# midi_io.net
KiCad netlist of a schematic drawn in EAGLE
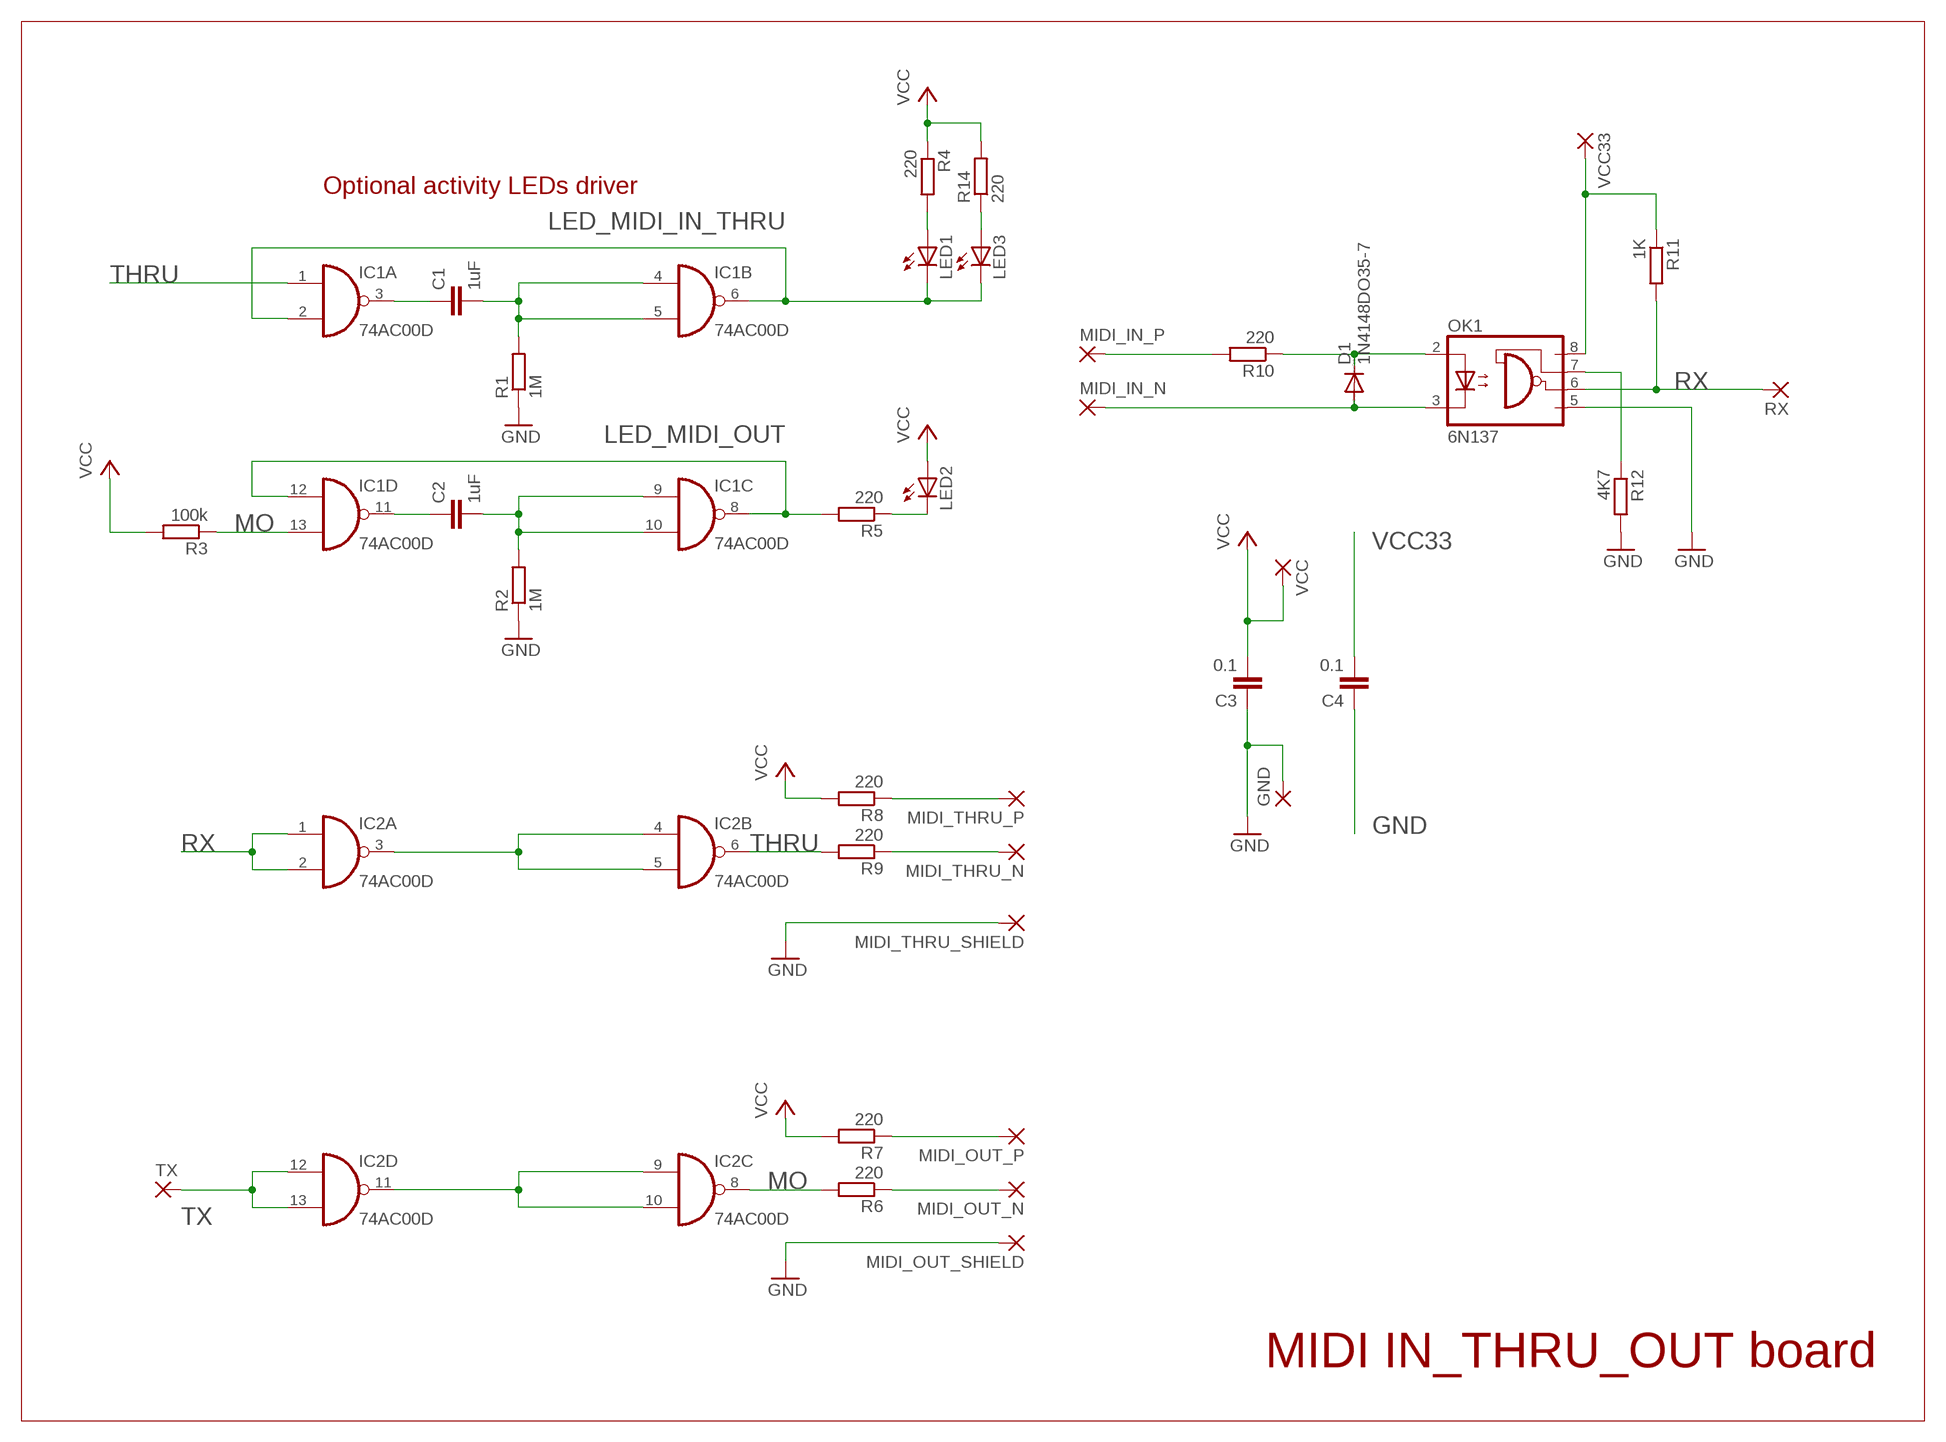
[diagram p0: schematic, sheet 1]

(export (version "E")
  (design (tool "Eeschema 10.0.6"))
  (components
    (comp (ref "C1")
      (value "1uF")
      (footprint "eagle-import:C0805")
      (libsource (lib "eagle-import") (part "C-EUC0805"))
    )
    (comp (ref "C2")
      (value "1uF")
      (footprint "eagle-import:C0805")
      (libsource (lib "eagle-import") (part "C-EUC0805"))
    )
    (comp (ref "C3")
      (value "0.1")
      (footprint "eagle-import:C0805")
      (libsource (lib "eagle-import") (part "C-EUC0805"))
    )
    (comp (ref "C4")
      (value "0.1")
      (footprint "eagle-import:C0805")
      (libsource (lib "eagle-import") (part "C-EUC0805"))
    )
    (comp (ref "D1")
      (value "1N4148DO35-7")
      (footprint "eagle-import:DO35-7")
      (libsource (lib "eagle-import") (part "1N4148DO35-7"))
    )
    (comp (ref "GND")
      (value "1,6/0,8")
      (footprint "eagle-import:1,6_0,8")
      (libsource (lib "eagle-import") (part "1,6/0,8"))
    )
    (comp (ref "IC1")
      (value "74AC00D")
      (footprint "eagle-import:SO14")
      (libsource (lib "eagle-import") (part "7400DAC"))
    )
    (comp (ref "IC2")
      (value "74AC00D")
      (footprint "eagle-import:SO14")
      (libsource (lib "eagle-import") (part "7400DAC"))
    )
    (comp (ref "LED1")
      (value "LED3MM")
      (footprint "eagle-import:LED3MM")
      (libsource (lib "eagle-import") (part "LED3MM"))
    )
    (comp (ref "LED2")
      (value "LED3MM")
      (footprint "eagle-import:LED3MM")
      (libsource (lib "eagle-import") (part "LED3MM"))
    )
    (comp (ref "LED3")
      (value "LED3MM")
      (footprint "eagle-import:LED3MM")
      (libsource (lib "eagle-import") (part "LED3MM"))
    )
    (comp (ref "MIDI_IN_N")
      (value "1,6/0,8")
      (footprint "eagle-import:1,6_0,8")
      (libsource (lib "eagle-import") (part "1,6/0,8"))
    )
    (comp (ref "MIDI_IN_P")
      (value "1,6/0,8")
      (footprint "eagle-import:1,6_0,8")
      (libsource (lib "eagle-import") (part "1,6/0,8"))
    )
    (comp (ref "MIDI_OUT_N")
      (value "1,6/0,8")
      (footprint "eagle-import:1,6_0,8")
      (libsource (lib "eagle-import") (part "1,6/0,8"))
    )
    (comp (ref "MIDI_OUT_P")
      (value "1,6/0,8")
      (footprint "eagle-import:1,6_0,8")
      (libsource (lib "eagle-import") (part "1,6/0,8"))
    )
    (comp (ref "MIDI_OUT_SHIELD")
      (value "1,6/0,8")
      (footprint "eagle-import:1,6_0,8")
      (libsource (lib "eagle-import") (part "1,6/0,8"))
    )
    (comp (ref "MIDI_THRU_N")
      (value "1,6/0,8")
      (footprint "eagle-import:1,6_0,8")
      (libsource (lib "eagle-import") (part "1,6/0,8"))
    )
    (comp (ref "MIDI_THRU_P")
      (value "1,6/0,8")
      (footprint "eagle-import:1,6_0,8")
      (libsource (lib "eagle-import") (part "1,6/0,8"))
    )
    (comp (ref "MIDI_THRU_SHIELD")
      (value "1,6/0,8")
      (footprint "eagle-import:1,6_0,8")
      (libsource (lib "eagle-import") (part "1,6/0,8"))
    )
    (comp (ref "OK1")
      (value "6N137")
      (footprint "eagle-import:DIL08")
      (libsource (lib "eagle-import") (part "6N137"))
    )
    (comp (ref "R1")
      (value "1M")
      (footprint "eagle-import:M0805")
      (libsource (lib "eagle-import") (part "R-EU_M0805"))
    )
    (comp (ref "R2")
      (value "1M")
      (footprint "eagle-import:M0805")
      (libsource (lib "eagle-import") (part "R-EU_M0805"))
    )
    (comp (ref "R3")
      (value "100k")
      (footprint "eagle-import:M0805")
      (libsource (lib "eagle-import") (part "R-EU_M0805"))
    )
    (comp (ref "R4")
      (value "220")
      (footprint "eagle-import:0204_7")
      (libsource (lib "eagle-import") (part "R-EU_0204/7"))
    )
    (comp (ref "R5")
      (value "220")
      (footprint "eagle-import:M0805")
      (libsource (lib "eagle-import") (part "R-EU_M0805"))
    )
    (comp (ref "R6")
      (value "220")
      (footprint "eagle-import:0204_7")
      (libsource (lib "eagle-import") (part "R-EU_0204/7"))
    )
    (comp (ref "R7")
      (value "220")
      (footprint "eagle-import:0204_7")
      (libsource (lib "eagle-import") (part "R-EU_0204/7"))
    )
    (comp (ref "R8")
      (value "220")
      (footprint "eagle-import:0204_7")
      (libsource (lib "eagle-import") (part "R-EU_0204/7"))
    )
    (comp (ref "R9")
      (value "220")
      (footprint "eagle-import:0204_7")
      (libsource (lib "eagle-import") (part "R-EU_0204/7"))
    )
    (comp (ref "R10")
      (value "220")
      (footprint "eagle-import:0204_7")
      (libsource (lib "eagle-import") (part "R-EU_0204/7"))
    )
    (comp (ref "R11")
      (value "1K")
      (footprint "eagle-import:0204_7")
      (libsource (lib "eagle-import") (part "R-EU_0204/7"))
    )
    (comp (ref "R12")
      (value "4K7")
      (footprint "eagle-import:0204_7")
      (libsource (lib "eagle-import") (part "R-EU_0204/7"))
    )
    (comp (ref "R14")
      (value "220")
      (footprint "eagle-import:0617_17")
      (libsource (lib "eagle-import") (part "R-EU_0617/17"))
    )
    (comp (ref "RX")
      (value "1,6/0,8")
      (footprint "eagle-import:1,6_0,8")
      (libsource (lib "eagle-import") (part "1,6/0,8"))
    )
    (comp (ref "TX")
      (value "1,6/0,8")
      (footprint "eagle-import:1,6_0,8")
      (libsource (lib "eagle-import") (part "1,6/0,8"))
    )
    (comp (ref "VCC")
      (value "1,6/0,8")
      (footprint "eagle-import:1,6_0,8")
      (libsource (lib "eagle-import") (part "1,6/0,8"))
    )
    (comp (ref "VCC33")
      (value "1,6/0,8")
      (footprint "eagle-import:1,6_0,8")
      (libsource (lib "eagle-import") (part "1,6/0,8"))
    )
  )
  (nets
    (net (code "1") (name "/LED_MIDI_IN_THRU") (class "Default")
      (node (ref "IC1") (pin "2") (pinfunction "I1_2") (pintype "input"))
      (node (ref "IC1") (pin "6") (pinfunction "O_6") (pintype "output"))
      (node (ref "LED1") (pin "K") (pinfunction "C_K") (pintype "passive"))
      (node (ref "LED3") (pin "K") (pinfunction "C_K") (pintype "passive"))
    )
    (net (code "2") (name "/LED_MIDI_OUT") (class "Default")
      (node (ref "IC1") (pin "12") (pinfunction "I0_12") (pintype "input"))
      (node (ref "IC1") (pin "8") (pinfunction "O_8") (pintype "output"))
      (node (ref "R5") (pin "2") (pinfunction "2_2") (pintype "passive"))
    )
    (net (code "3") (name "/MO") (class "Default")
      (node (ref "IC1") (pin "13") (pinfunction "I1_13") (pintype "input"))
      (node (ref "IC2") (pin "8") (pinfunction "O_8") (pintype "output"))
      (node (ref "R3") (pin "1") (pinfunction "1_1") (pintype "passive"))
      (node (ref "R6") (pin "2") (pinfunction "2_2") (pintype "passive"))
    )
    (net (code "4") (name "/RX") (class "Default")
      (node (ref "IC2") (pin "1") (pinfunction "I0_1") (pintype "input"))
      (node (ref "IC2") (pin "2") (pinfunction "I1_2") (pintype "input"))
      (node (ref "OK1") (pin "6") (pinfunction "VO_6") (pintype "passive"))
      (node (ref "R11") (pin "2") (pinfunction "2_2") (pintype "passive"))
      (node (ref "RX") (pin "1") (pinfunction "P_1") (pintype "passive"))
    )
    (net (code "5") (name "/THRU") (class "Default")
      (node (ref "IC1") (pin "1") (pinfunction "I0_1") (pintype "input"))
      (node (ref "IC2") (pin "6") (pinfunction "O_6") (pintype "output"))
      (node (ref "R9") (pin "2") (pinfunction "2_2") (pintype "passive"))
    )
    (net (code "6") (name "/TX") (class "Default")
      (node (ref "IC2") (pin "12") (pinfunction "I0_12") (pintype "input"))
      (node (ref "IC2") (pin "13") (pinfunction "I1_13") (pintype "input"))
      (node (ref "TX") (pin "1") (pinfunction "P_1") (pintype "passive"))
    )
    (net (code "7") (name "/VCC33") (class "Default")
      (node (ref "C4") (pin "2") (pinfunction "2_2") (pintype "passive"))
      (node (ref "OK1") (pin "8") (pinfunction "VCC_8") (pintype "passive"))
      (node (ref "R11") (pin "1") (pinfunction "1_1") (pintype "passive"))
      (node (ref "VCC33") (pin "1") (pinfunction "P_1") (pintype "passive"))
    )
    (net (code "8") (name "GND") (class "Default")
      (node (ref "C3") (pin "1") (pinfunction "1_1") (pintype "passive"))
      (node (ref "C4") (pin "1") (pinfunction "1_1") (pintype "passive"))
      (node (ref "GND") (pin "1") (pinfunction "P_1") (pintype "passive"))
      (node (ref "MIDI_OUT_SHIELD") (pin "1") (pinfunction "P_1") (pintype "passive"))
      (node (ref "MIDI_THRU_SHIELD") (pin "1") (pinfunction "P_1") (pintype "passive"))
      (node (ref "OK1") (pin "5") (pinfunction "GND_5") (pintype "passive"))
      (node (ref "R1") (pin "1") (pinfunction "1_1") (pintype "passive"))
      (node (ref "R12") (pin "2") (pinfunction "2_2") (pintype "passive"))
      (node (ref "R2") (pin "1") (pinfunction "1_1") (pintype "passive"))
    )
    (net (code "9") (name "Net-(IC1A-O)") (class "Default")
      (node (ref "C1") (pin "1") (pinfunction "1_1") (pintype "passive"))
      (node (ref "IC1") (pin "3") (pinfunction "O_3") (pintype "output"))
    )
    (net (code "10") (name "Net-(IC1B-I0)") (class "Default")
      (node (ref "C1") (pin "2") (pinfunction "2_2") (pintype "passive"))
      (node (ref "IC1") (pin "4") (pinfunction "I0_4") (pintype "input"))
      (node (ref "IC1") (pin "5") (pinfunction "I1_5") (pintype "input"))
      (node (ref "R1") (pin "2") (pinfunction "2_2") (pintype "passive"))
    )
    (net (code "11") (name "Net-(IC1C-I0)") (class "Default")
      (node (ref "C2") (pin "2") (pinfunction "2_2") (pintype "passive"))
      (node (ref "IC1") (pin "10") (pinfunction "I1_10") (pintype "input"))
      (node (ref "IC1") (pin "9") (pinfunction "I0_9") (pintype "input"))
      (node (ref "R2") (pin "2") (pinfunction "2_2") (pintype "passive"))
    )
    (net (code "12") (name "Net-(IC1D-O)") (class "Default")
      (node (ref "C2") (pin "1") (pinfunction "1_1") (pintype "passive"))
      (node (ref "IC1") (pin "11") (pinfunction "O_11") (pintype "output"))
    )
    (net (code "13") (name "Net-(IC2A-O)") (class "Default")
      (node (ref "IC2") (pin "3") (pinfunction "O_3") (pintype "output"))
      (node (ref "IC2") (pin "4") (pinfunction "I0_4") (pintype "input"))
      (node (ref "IC2") (pin "5") (pinfunction "I1_5") (pintype "input"))
    )
    (net (code "14") (name "Net-(IC2C-I0)") (class "Default")
      (node (ref "IC2") (pin "10") (pinfunction "I1_10") (pintype "input"))
      (node (ref "IC2") (pin "11") (pinfunction "O_11") (pintype "output"))
      (node (ref "IC2") (pin "9") (pinfunction "I0_9") (pintype "input"))
    )
    (net (code "15") (name "Net-(LED1-PadA)") (class "Default")
      (node (ref "LED1") (pin "A") (pinfunction "A_A") (pintype "passive"))
      (node (ref "R4") (pin "2") (pinfunction "2_2") (pintype "passive"))
    )
    (net (code "16") (name "Net-(LED2-C)") (class "Default")
      (node (ref "LED2") (pin "K") (pinfunction "C_K") (pintype "passive"))
      (node (ref "R5") (pin "1") (pinfunction "1_1") (pintype "passive"))
    )
    (net (code "17") (name "Net-(LED3-PadA)") (class "Default")
      (node (ref "LED3") (pin "A") (pinfunction "A_A") (pintype "passive"))
      (node (ref "R14") (pin "1") (pinfunction "1_1") (pintype "passive"))
    )
    (net (code "18") (name "Net-(MIDI_IN_N-P)") (class "Default")
      (node (ref "D1") (pin "A") (pinfunction "A_A") (pintype "passive"))
      (node (ref "MIDI_IN_N") (pin "1") (pinfunction "P_1") (pintype "passive"))
      (node (ref "OK1") (pin "3") (pinfunction "C_3") (pintype "passive"))
    )
    (net (code "19") (name "Net-(MIDI_IN_P-P)") (class "Default")
      (node (ref "MIDI_IN_P") (pin "1") (pinfunction "P_1") (pintype "passive"))
      (node (ref "R10") (pin "2") (pinfunction "2_2") (pintype "passive"))
    )
    (net (code "20") (name "Net-(MIDI_OUT_N-P)") (class "Default")
      (node (ref "MIDI_OUT_N") (pin "1") (pinfunction "P_1") (pintype "passive"))
      (node (ref "R6") (pin "1") (pinfunction "1_1") (pintype "passive"))
    )
    (net (code "21") (name "Net-(MIDI_OUT_P-P)") (class "Default")
      (node (ref "MIDI_OUT_P") (pin "1") (pinfunction "P_1") (pintype "passive"))
      (node (ref "R7") (pin "1") (pinfunction "1_1") (pintype "passive"))
    )
    (net (code "22") (name "Net-(MIDI_THRU_N-P)") (class "Default")
      (node (ref "MIDI_THRU_N") (pin "1") (pinfunction "P_1") (pintype "passive"))
      (node (ref "R9") (pin "1") (pinfunction "1_1") (pintype "passive"))
    )
    (net (code "23") (name "Net-(MIDI_THRU_P-P)") (class "Default")
      (node (ref "MIDI_THRU_P") (pin "1") (pinfunction "P_1") (pintype "passive"))
      (node (ref "R8") (pin "1") (pinfunction "1_1") (pintype "passive"))
    )
    (net (code "24") (name "Net-(OK1-A)") (class "Default")
      (node (ref "D1") (pin "C") (pinfunction "C_C") (pintype "passive"))
      (node (ref "OK1") (pin "2") (pinfunction "A_2") (pintype "passive"))
      (node (ref "R10") (pin "1") (pinfunction "1_1") (pintype "passive"))
    )
    (net (code "25") (name "Net-(OK1-VE)") (class "Default")
      (node (ref "OK1") (pin "7") (pinfunction "VE_7") (pintype "passive"))
      (node (ref "R12") (pin "1") (pinfunction "1_1") (pintype "passive"))
    )
    (net (code "26") (name "VCC") (class "Default")
      (node (ref "C3") (pin "2") (pinfunction "2_2") (pintype "passive"))
      (node (ref "LED2") (pin "A") (pinfunction "A_A") (pintype "passive"))
      (node (ref "R14") (pin "2") (pinfunction "2_2") (pintype "passive"))
      (node (ref "R3") (pin "2") (pinfunction "2_2") (pintype "passive"))
      (node (ref "R4") (pin "1") (pinfunction "1_1") (pintype "passive"))
      (node (ref "R7") (pin "2") (pinfunction "2_2") (pintype "passive"))
      (node (ref "R8") (pin "2") (pinfunction "2_2") (pintype "passive"))
      (node (ref "VCC") (pin "1") (pinfunction "P_1") (pintype "passive"))
    )
  )
)
